# ESP-Breakout.net
KiCad netlist of a schematic drawn in EAGLE
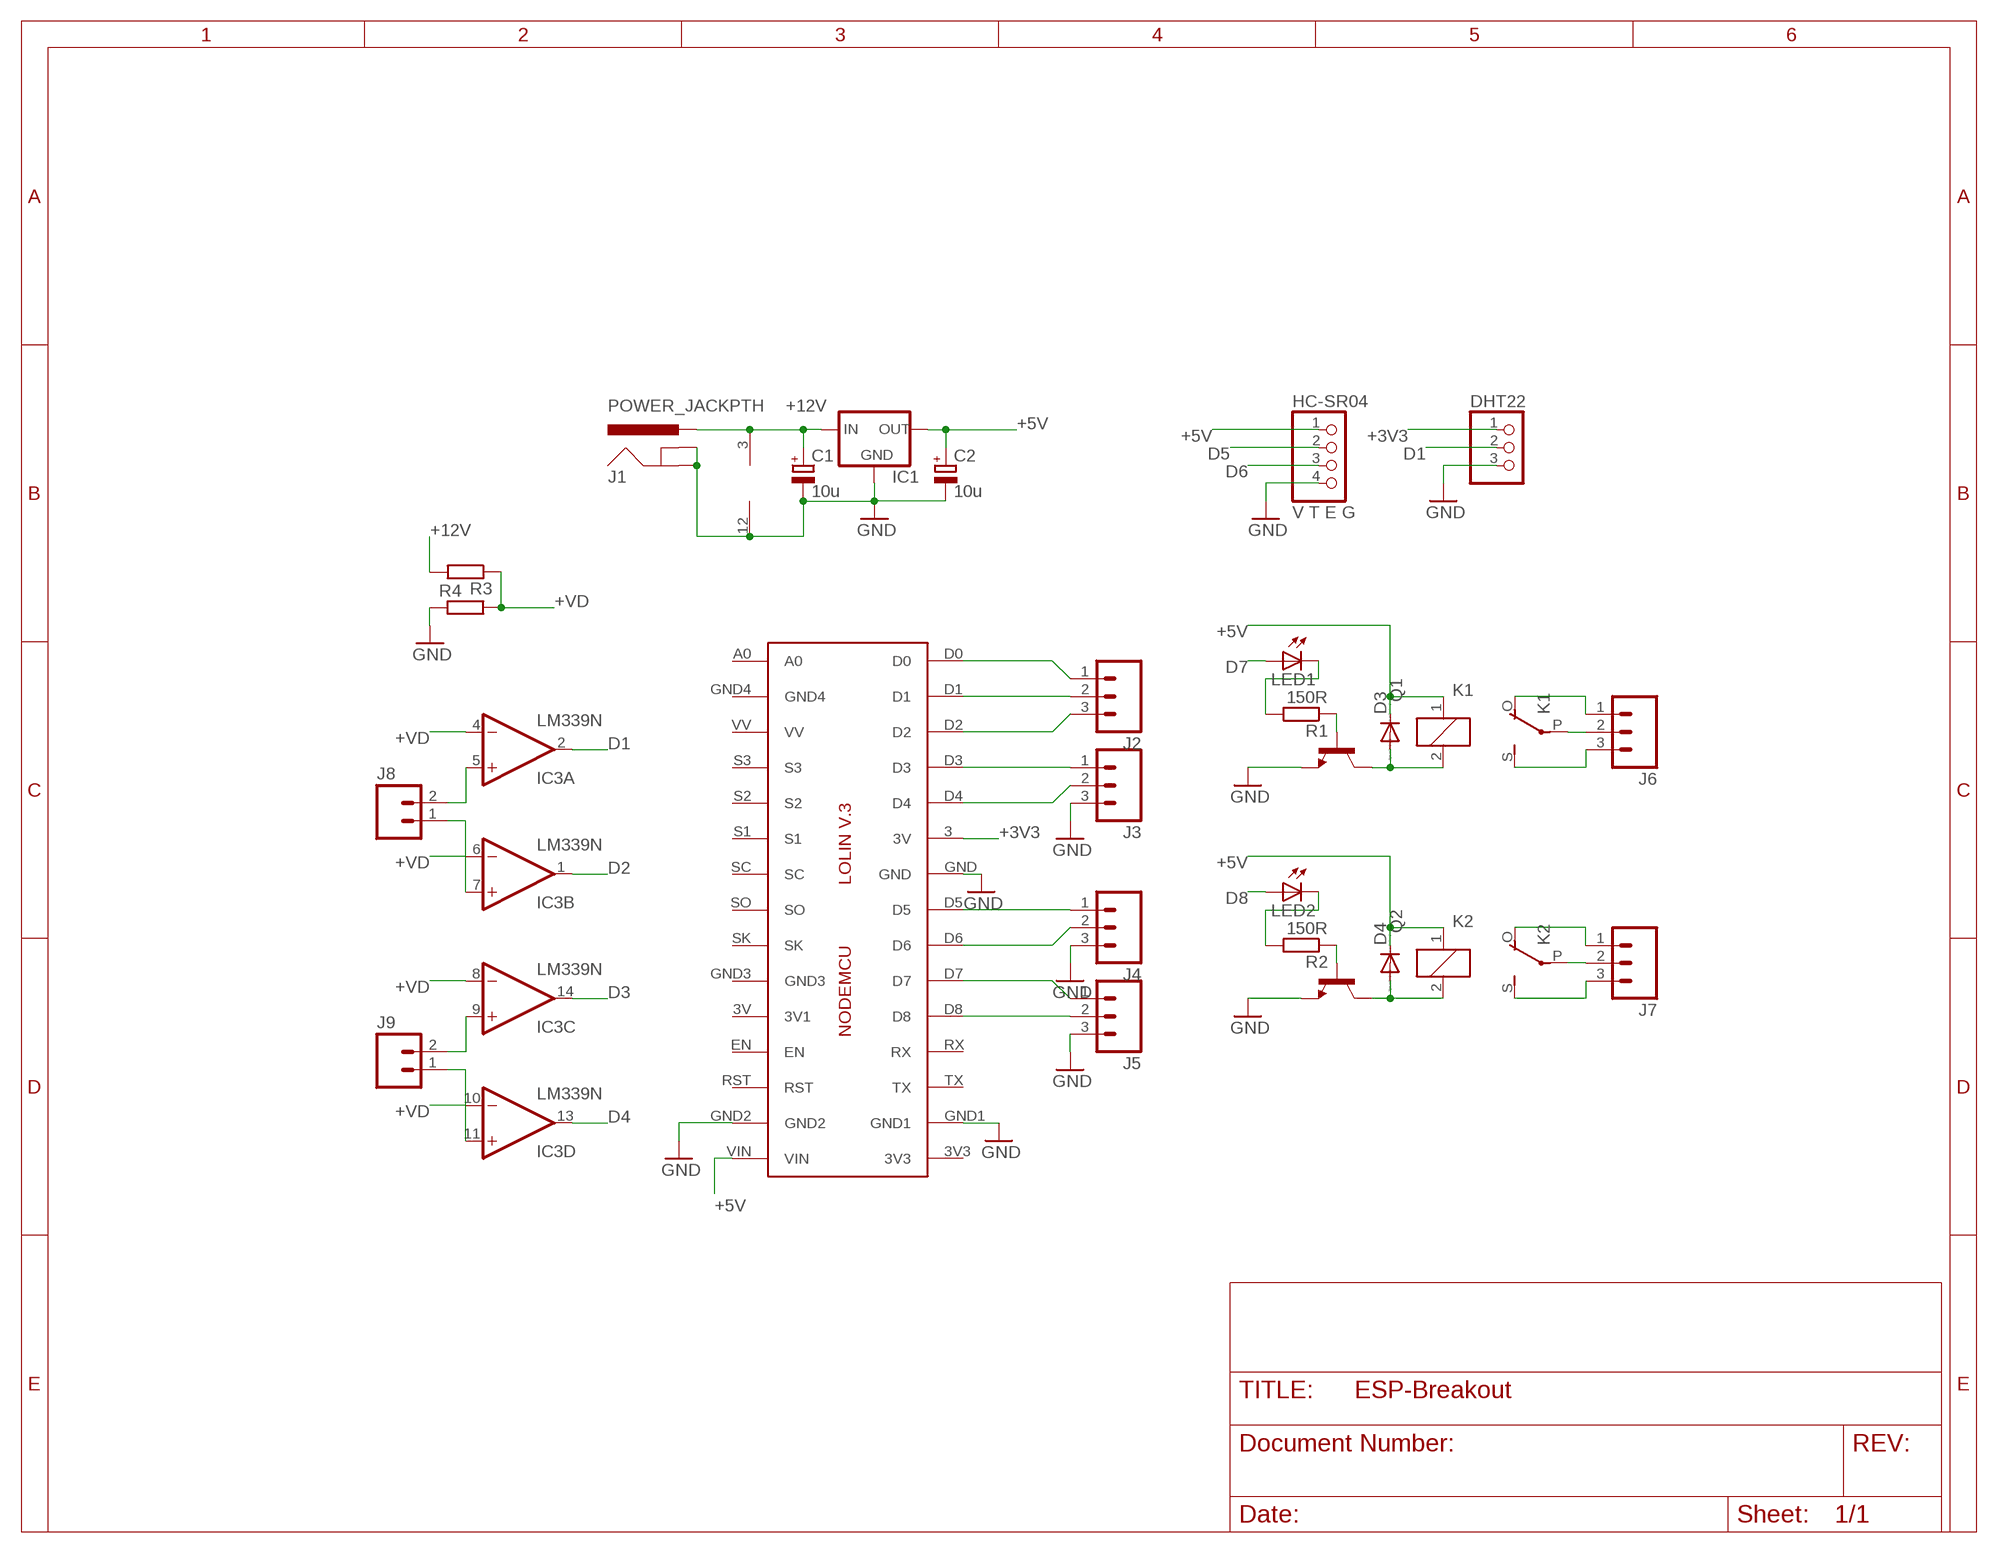
[diagram p0: schematic, sheet 1]

(export (version "E")
  (design (tool "Eeschema 10.0.6"))
  (components
    (comp (ref "C1")
      (value "10u")
      (footprint "eagle-import:A_3216-18W")
      (libsource (lib "eagle-import") (part "CPOL-EUA/3216-18W"))
    )
    (comp (ref "C2")
      (value "10u")
      (footprint "eagle-import:A_3216-18W")
      (libsource (lib "eagle-import") (part "CPOL-EUA/3216-18W"))
    )
    (comp (ref "D3")
      (value "DIODE-DO214AC")
      (footprint "eagle-import:DO214AC")
      (libsource (lib "eagle-import") (part "DIODE-DO214AC"))
    )
    (comp (ref "D4")
      (value "DIODE-DO214AC")
      (footprint "eagle-import:DO214AC")
      (libsource (lib "eagle-import") (part "DIODE-DO214AC"))
    )
    (comp (ref "DHT22")
      (value "PINHD-1X3/90")
      (footprint "eagle-import:1X03_90")
      (libsource (lib "eagle-import") (part "PINHD-1X3/90"))
    )
    (comp (ref "HC-SR04")
      (value "V T E G")
      (footprint "eagle-import:1X04")
      (libsource (lib "eagle-import") (part "PINHD-1X4"))
    )
    (comp (ref "IC1")
      (value "LM1117")
      (footprint "eagle-import:SOT223")
      (libsource (lib "eagle-import") (part "LM1117"))
    )
    (comp (ref "IC2")
      (value "LOLINV3")
      (footprint "eagle-import:LOLINV3")
      (libsource (lib "eagle-import") (part "LOLINV3"))
    )
    (comp (ref "IC3")
      (value "LM339N")
      (footprint "eagle-import:DIL14")
      (libsource (lib "eagle-import") (part "LM339N"))
    )
    (comp (ref "J1")
      (value "POWER_JACKPTH")
      (footprint "eagle-import:POWER_JACK_PTH")
      (libsource (lib "eagle-import") (part "POWER_JACKPTH"))
    )
    (comp (ref "J2")
      (value "M03-SCREW-5MM")
      (footprint "eagle-import:SCREWTERMINAL-5MM-3")
      (libsource (lib "eagle-import") (part "M03-SCREW-5MM"))
    )
    (comp (ref "J3")
      (value "M03-SCREW-5MM")
      (footprint "eagle-import:SCREWTERMINAL-5MM-3")
      (libsource (lib "eagle-import") (part "M03-SCREW-5MM"))
    )
    (comp (ref "J4")
      (value "M03-SCREW-5MM")
      (footprint "eagle-import:SCREWTERMINAL-5MM-3")
      (libsource (lib "eagle-import") (part "M03-SCREW-5MM"))
    )
    (comp (ref "J5")
      (value "M03-SCREW-5MM")
      (footprint "eagle-import:SCREWTERMINAL-5MM-3")
      (libsource (lib "eagle-import") (part "M03-SCREW-5MM"))
    )
    (comp (ref "J6")
      (value "M03-SCREW-5MM")
      (footprint "eagle-import:SCREWTERMINAL-5MM-3")
      (libsource (lib "eagle-import") (part "M03-SCREW-5MM"))
    )
    (comp (ref "J7")
      (value "M03-SCREW-5MM")
      (footprint "eagle-import:SCREWTERMINAL-5MM-3")
      (libsource (lib "eagle-import") (part "M03-SCREW-5MM"))
    )
    (comp (ref "J8")
      (value "M025MM")
      (footprint "eagle-import:SCREWTERMINAL-5MM-2")
      (libsource (lib "eagle-import") (part "M025MM"))
    )
    (comp (ref "J9")
      (value "M025MM")
      (footprint "eagle-import:SCREWTERMINAL-5MM-2")
      (libsource (lib "eagle-import") (part "M025MM"))
    )
    (comp (ref "K1")
      (value "ZF112")
      (footprint "eagle-import:ZF112")
      (libsource (lib "eagle-import") (part "ZF112"))
    )
    (comp (ref "K2")
      (value "ZF112")
      (footprint "eagle-import:ZF112")
      (libsource (lib "eagle-import") (part "ZF112"))
    )
    (comp (ref "LED1")
      (value "LEDCHIP-LED0805")
      (footprint "eagle-import:CHIP-LED0805")
      (libsource (lib "eagle-import") (part "LEDCHIP-LED0805"))
    )
    (comp (ref "LED2")
      (value "LEDCHIP-LED0805")
      (footprint "eagle-import:CHIP-LED0805")
      (libsource (lib "eagle-import") (part "LEDCHIP-LED0805"))
    )
    (comp (ref "Q1")
      (value "BC850SMD")
      (footprint "eagle-import:SOT23-BEC")
      (libsource (lib "eagle-import") (part "BC850SMD"))
    )
    (comp (ref "Q2")
      (value "BC850SMD")
      (footprint "eagle-import:SOT23-BEC")
      (libsource (lib "eagle-import") (part "BC850SMD"))
    )
    (comp (ref "R1")
      (value "150R")
      (footprint "eagle-import:R0805")
      (libsource (lib "eagle-import") (part "R-EU_R0805"))
    )
    (comp (ref "R2")
      (value "150R")
      (footprint "eagle-import:R0805")
      (libsource (lib "eagle-import") (part "R-EU_R0805"))
    )
    (comp (ref "R3")
      (value "R-EU_0204/7")
      (footprint "eagle-import:0204_7")
      (libsource (lib "eagle-import") (part "R-EU_0204/7"))
    )
    (comp (ref "R4")
      (value "R-EU_0204/7")
      (footprint "eagle-import:0204_7")
      (libsource (lib "eagle-import") (part "R-EU_0204/7"))
    )
  )
  (nets
    (net (code "1") (name "/+3V3") (class "Default")
      (node (ref "DHT22") (pin "1") (pinfunction "1_1") (pintype "passive"))
      (node (ref "IC2") (pin "3") (pinfunction "3V_3") (pintype "bidirectional"))
    )
    (net (code "2") (name "/+5V") (class "Default")
      (node (ref "C2") (pin "+") (pinfunction "+_+") (pintype "passive"))
      (node (ref "D3") (pin "C") (pinfunction "C_C") (pintype "passive"))
      (node (ref "D4") (pin "C") (pinfunction "C_C") (pintype "passive"))
      (node (ref "HC-SR04") (pin "1") (pinfunction "1_1") (pintype "passive"))
      (node (ref "IC1") (pin "2") (pinfunction "OUT_2") (pintype "passive"))
      (node (ref "IC2") (pin "VIN") (pinfunction "VIN_VIN") (pintype "bidirectional"))
      (node (ref "K1") (pin "1") (pinfunction "1_1") (pintype "passive"))
      (node (ref "K2") (pin "1") (pinfunction "1_1") (pintype "passive"))
    )
    (net (code "3") (name "/+12V") (class "Default")
      (node (ref "C1") (pin "+") (pinfunction "+_+") (pintype "passive"))
      (node (ref "IC1") (pin "3") (pinfunction "IN_3") (pintype "input"))
      (node (ref "IC3") (pin "3") (pinfunction "V+_3") (pintype "power_in"))
      (node (ref "J1") (pin "PWR") (pinfunction "PWR_PWR") (pintype "bidirectional"))
      (node (ref "R3") (pin "2") (pinfunction "2_2") (pintype "passive"))
    )
    (net (code "4") (name "/+VD") (class "Default")
      (node (ref "IC3") (pin "10") (pinfunction "-IN_10") (pintype "input"))
      (node (ref "IC3") (pin "4") (pinfunction "-IN_4") (pintype "input"))
      (node (ref "IC3") (pin "6") (pinfunction "-IN_6") (pintype "input"))
      (node (ref "IC3") (pin "8") (pinfunction "-IN_8") (pintype "input"))
      (node (ref "R3") (pin "1") (pinfunction "1_1") (pintype "passive"))
      (node (ref "R4") (pin "2") (pinfunction "2_2") (pintype "passive"))
    )
    (net (code "5") (name "/D1") (class "Default")
      (node (ref "DHT22") (pin "2") (pinfunction "2_2") (pintype "passive"))
      (node (ref "IC2") (pin "D1") (pinfunction "D1_D1") (pintype "bidirectional"))
      (node (ref "IC3") (pin "2") (pinfunction "OUT_2") (pintype "open_collector"))
      (node (ref "J2") (pin "2") (pinfunction "2_2") (pintype "passive"))
    )
    (net (code "6") (name "/D2") (class "Default")
      (node (ref "IC2") (pin "D2") (pinfunction "D2_D2") (pintype "bidirectional"))
      (node (ref "IC3") (pin "1") (pinfunction "OUT_1") (pintype "open_collector"))
      (node (ref "J2") (pin "3") (pinfunction "3_3") (pintype "passive"))
    )
    (net (code "7") (name "/D3") (class "Default")
      (node (ref "IC2") (pin "D3") (pinfunction "D3_D3") (pintype "bidirectional"))
      (node (ref "IC3") (pin "14") (pinfunction "OUT_14") (pintype "open_collector"))
      (node (ref "J3") (pin "1") (pinfunction "1_1") (pintype "passive"))
    )
    (net (code "8") (name "/D4") (class "Default")
      (node (ref "IC2") (pin "D4") (pinfunction "D4_D4") (pintype "bidirectional"))
      (node (ref "IC3") (pin "13") (pinfunction "OUT_13") (pintype "open_collector"))
      (node (ref "J3") (pin "2") (pinfunction "2_2") (pintype "passive"))
    )
    (net (code "9") (name "/D5") (class "Default")
      (node (ref "HC-SR04") (pin "2") (pinfunction "2_2") (pintype "passive"))
      (node (ref "IC2") (pin "D5") (pinfunction "D5_D5") (pintype "bidirectional"))
      (node (ref "J4") (pin "1") (pinfunction "1_1") (pintype "passive"))
    )
    (net (code "10") (name "/D6") (class "Default")
      (node (ref "HC-SR04") (pin "3") (pinfunction "3_3") (pintype "passive"))
      (node (ref "IC2") (pin "D6") (pinfunction "D6_D6") (pintype "bidirectional"))
      (node (ref "J4") (pin "2") (pinfunction "2_2") (pintype "passive"))
    )
    (net (code "11") (name "/D7") (class "Default")
      (node (ref "IC2") (pin "D7") (pinfunction "D7_D7") (pintype "bidirectional"))
      (node (ref "J5") (pin "1") (pinfunction "1_1") (pintype "passive"))
      (node (ref "LED1") (pin "A") (pinfunction "A_A") (pintype "passive"))
    )
    (net (code "12") (name "/D8") (class "Default")
      (node (ref "IC2") (pin "D8") (pinfunction "D8_D8") (pintype "bidirectional"))
      (node (ref "J5") (pin "2") (pinfunction "2_2") (pintype "passive"))
      (node (ref "LED2") (pin "A") (pinfunction "A_A") (pintype "passive"))
    )
    (net (code "13") (name "GND") (class "Default")
      (node (ref "C1") (pin "-") (pinfunction "-_-") (pintype "passive"))
      (node (ref "C2") (pin "-") (pinfunction "-_-") (pintype "passive"))
      (node (ref "DHT22") (pin "3") (pinfunction "3_3") (pintype "passive"))
      (node (ref "HC-SR04") (pin "4") (pinfunction "4_4") (pintype "passive"))
      (node (ref "IC1") (pin "1") (pinfunction "GND_1") (pintype "input"))
      (node (ref "IC2") (pin "GND") (pinfunction "GND_GND") (pintype "bidirectional"))
      (node (ref "IC2") (pin "GND1") (pinfunction "GND1_GND1") (pintype "bidirectional"))
      (node (ref "IC2") (pin "GND2") (pinfunction "GND2_GND2") (pintype "bidirectional"))
      (node (ref "IC3") (pin "12") (pinfunction "GND_12") (pintype "power_in"))
      (node (ref "J1") (pin "GND") (pinfunction "GND_GND") (pintype "bidirectional"))
      (node (ref "J1") (pin "GNDBREAK") (pinfunction "GNDBREAK_GNDBREAK") (pintype "bidirectional"))
      (node (ref "J3") (pin "3") (pinfunction "3_3") (pintype "passive"))
      (node (ref "J4") (pin "3") (pinfunction "3_3") (pintype "passive"))
      (node (ref "J5") (pin "3") (pinfunction "3_3") (pintype "passive"))
      (node (ref "Q1") (pin "E") (pinfunction "E_E") (pintype "passive"))
      (node (ref "Q2") (pin "E") (pinfunction "E_E") (pintype "passive"))
      (node (ref "R4") (pin "1") (pinfunction "1_1") (pintype "passive"))
    )
    (net (code "14") (name "Net-(D3-PadA)") (class "Default")
      (node (ref "D3") (pin "A") (pinfunction "A_A") (pintype "passive"))
      (node (ref "K1") (pin "2") (pinfunction "2_2") (pintype "passive"))
      (node (ref "Q1") (pin "C") (pinfunction "C_C") (pintype "passive"))
    )
    (net (code "15") (name "Net-(D4-PadA)") (class "Default")
      (node (ref "D4") (pin "A") (pinfunction "A_A") (pintype "passive"))
      (node (ref "K2") (pin "2") (pinfunction "2_2") (pintype "passive"))
      (node (ref "Q2") (pin "C") (pinfunction "C_C") (pintype "passive"))
    )
    (net (code "16") (name "Net-(IC2-PadD0)") (class "Default")
      (node (ref "IC2") (pin "D0") (pinfunction "D0_D0") (pintype "bidirectional"))
      (node (ref "J2") (pin "1") (pinfunction "1_1") (pintype "passive"))
    )
    (net (code "17") (name "Net-(IC3A-+IN)") (class "Default")
      (node (ref "IC3") (pin "5") (pinfunction "+IN_5") (pintype "input"))
      (node (ref "J8") (pin "2") (pinfunction "2_2") (pintype "passive"))
    )
    (net (code "18") (name "Net-(IC3B-+IN)") (class "Default")
      (node (ref "IC3") (pin "7") (pinfunction "+IN_7") (pintype "input"))
      (node (ref "J8") (pin "1") (pinfunction "1_1") (pintype "passive"))
    )
    (net (code "19") (name "Net-(IC3C-+IN)") (class "Default")
      (node (ref "IC3") (pin "9") (pinfunction "+IN_9") (pintype "input"))
      (node (ref "J9") (pin "2") (pinfunction "2_2") (pintype "passive"))
    )
    (net (code "20") (name "Net-(IC3D-+IN)") (class "Default")
      (node (ref "IC3") (pin "11") (pinfunction "+IN_11") (pintype "input"))
      (node (ref "J9") (pin "1") (pinfunction "1_1") (pintype "passive"))
    )
    (net (code "21") (name "Net-(J6-Pad1)") (class "Default")
      (node (ref "J6") (pin "1") (pinfunction "1_1") (pintype "passive"))
      (node (ref "K1") (pin "O") (pinfunction "O_O") (pintype "passive"))
    )
    (net (code "22") (name "Net-(J6-Pad2)") (class "Default")
      (node (ref "J6") (pin "2") (pinfunction "2_2") (pintype "passive"))
      (node (ref "K1") (pin "P") (pinfunction "P_P") (pintype "passive"))
    )
    (net (code "23") (name "Net-(J6-Pad3)") (class "Default")
      (node (ref "J6") (pin "3") (pinfunction "3_3") (pintype "passive"))
      (node (ref "K1") (pin "S") (pinfunction "S_S") (pintype "passive"))
    )
    (net (code "24") (name "Net-(J7-Pad1)") (class "Default")
      (node (ref "J7") (pin "1") (pinfunction "1_1") (pintype "passive"))
      (node (ref "K2") (pin "O") (pinfunction "O_O") (pintype "passive"))
    )
    (net (code "25") (name "Net-(J7-Pad2)") (class "Default")
      (node (ref "J7") (pin "2") (pinfunction "2_2") (pintype "passive"))
      (node (ref "K2") (pin "P") (pinfunction "P_P") (pintype "passive"))
    )
    (net (code "26") (name "Net-(J7-Pad3)") (class "Default")
      (node (ref "J7") (pin "3") (pinfunction "3_3") (pintype "passive"))
      (node (ref "K2") (pin "S") (pinfunction "S_S") (pintype "passive"))
    )
    (net (code "27") (name "Net-(LED1-PadC)") (class "Default")
      (node (ref "LED1") (pin "C") (pinfunction "C_C") (pintype "passive"))
      (node (ref "R1") (pin "2") (pinfunction "2_2") (pintype "passive"))
    )
    (net (code "28") (name "Net-(LED2-PadC)") (class "Default")
      (node (ref "LED2") (pin "C") (pinfunction "C_C") (pintype "passive"))
      (node (ref "R2") (pin "2") (pinfunction "2_2") (pintype "passive"))
    )
    (net (code "29") (name "Net-(Q1-PadB)") (class "Default")
      (node (ref "Q1") (pin "B") (pinfunction "B_B") (pintype "passive"))
      (node (ref "R1") (pin "1") (pinfunction "1_1") (pintype "passive"))
    )
    (net (code "30") (name "Net-(Q2-PadB)") (class "Default")
      (node (ref "Q2") (pin "B") (pinfunction "B_B") (pintype "passive"))
      (node (ref "R2") (pin "1") (pinfunction "1_1") (pintype "passive"))
    )
    (net (code "31") (name "unconnected-(IC2-3V1-Pad3V)") (class "Default")
      (node (ref "IC2") (pin "3V") (pinfunction "3V1_3V") (pintype "bidirectional"))
    )
    (net (code "32") (name "unconnected-(IC2-Pad3V3)") (class "Default")
      (node (ref "IC2") (pin "3V3") (pinfunction "3V3_3V3") (pintype "bidirectional"))
    )
    (net (code "33") (name "unconnected-(IC2-PadA0)") (class "Default")
      (node (ref "IC2") (pin "A0") (pinfunction "A0_A0") (pintype "bidirectional"))
    )
    (net (code "34") (name "unconnected-(IC2-PadEN)") (class "Default")
      (node (ref "IC2") (pin "EN") (pinfunction "EN_EN") (pintype "bidirectional"))
    )
    (net (code "35") (name "unconnected-(IC2-PadGND3)") (class "Default")
      (node (ref "IC2") (pin "GND3") (pinfunction "GND3_GND3") (pintype "bidirectional"))
    )
    (net (code "36") (name "unconnected-(IC2-PadGND4)") (class "Default")
      (node (ref "IC2") (pin "GND4") (pinfunction "GND4_GND4") (pintype "bidirectional"))
    )
    (net (code "37") (name "unconnected-(IC2-PadRST)") (class "Default")
      (node (ref "IC2") (pin "RST") (pinfunction "RST_RST") (pintype "bidirectional"))
    )
    (net (code "38") (name "unconnected-(IC2-PadRX)") (class "Default")
      (node (ref "IC2") (pin "RX") (pinfunction "RX_RX") (pintype "bidirectional"))
    )
    (net (code "39") (name "unconnected-(IC2-PadS1)") (class "Default")
      (node (ref "IC2") (pin "S1") (pinfunction "S1_S1") (pintype "bidirectional"))
    )
    (net (code "40") (name "unconnected-(IC2-PadS2)") (class "Default")
      (node (ref "IC2") (pin "S2") (pinfunction "S2_S2") (pintype "bidirectional"))
    )
    (net (code "41") (name "unconnected-(IC2-PadS3)") (class "Default")
      (node (ref "IC2") (pin "S3") (pinfunction "S3_S3") (pintype "bidirectional"))
    )
    (net (code "42") (name "unconnected-(IC2-PadSC)") (class "Default")
      (node (ref "IC2") (pin "SC") (pinfunction "SC_SC") (pintype "bidirectional"))
    )
    (net (code "43") (name "unconnected-(IC2-PadSK)") (class "Default")
      (node (ref "IC2") (pin "SK") (pinfunction "SK_SK") (pintype "bidirectional"))
    )
    (net (code "44") (name "unconnected-(IC2-PadSO)") (class "Default")
      (node (ref "IC2") (pin "SO") (pinfunction "SO_SO") (pintype "bidirectional"))
    )
    (net (code "45") (name "unconnected-(IC2-PadTX)") (class "Default")
      (node (ref "IC2") (pin "TX") (pinfunction "TX_TX") (pintype "bidirectional"))
    )
    (net (code "46") (name "unconnected-(IC2-PadVV)") (class "Default")
      (node (ref "IC2") (pin "VV") (pinfunction "VV_VV") (pintype "bidirectional"))
    )
  )
)
